# Sheet1.net
KiCad netlist of a schematic drawn in Altium Designer
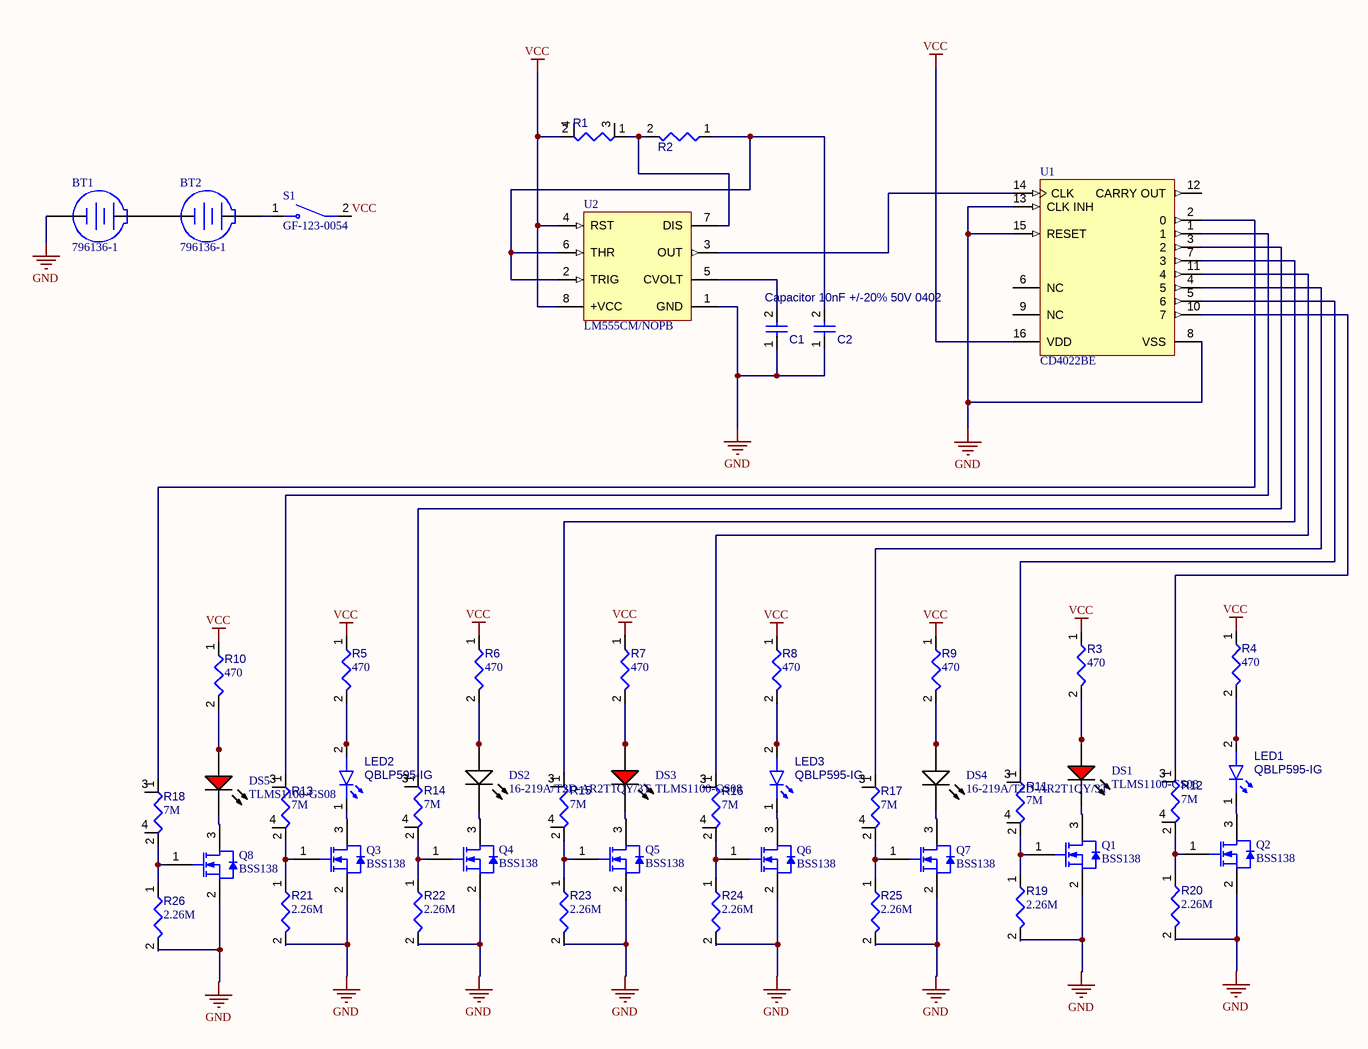
[diagram p0: Sheet1.SchDoc]

(export (version "E")
  (design (tool "Eeschema 10.0.6"))
  (components
    (comp (ref "BT1")
      (value "796136-1")
      (footprint "TECO-796136-1_V")
      (description "Battery Connector, 1 Cell, CR2032, 2-Pin SMD, RoHS, Tape and Reel")
      (fields (field (name "MANUFACTURER") "TE Connectivity"))
      (libsource (lib "Actalent") (part "BATTERY-HOLDER-COIN-2"))
    )
    (comp (ref "BT2")
      (value "796136-1")
      (footprint "TECO-796136-1_V")
      (description "Battery Connector, 1 Cell, CR2032, 2-Pin SMD, RoHS, Tape and Reel")
      (fields (field (name "MANUFACTURER") "TE Connectivity"))
      (libsource (lib "Actalent") (part "BATTERY-HOLDER-COIN-2"))
    )
    (comp (ref "C1")
      (value "Capacitor 10nF +/-20% 50V 0402")
      (footprint "CAPC0402(1005)60_L")
      (description "Chip Capacitor, 10nF +/-20%, 50V, 0402, Thickness 0.6 mm")
      (fields (field (name "TOLERANCE") "5%"))
      (libsource (lib "Actalent") (part "CAP-NP-2"))
    )
    (comp (ref "C2")
      (value "Capacitor 100 nF +/-10% 50 V 0805")
      (footprint "CAPC2013X95X50LL10T25")
      (description "Chip Capacitor, 100 nF, +/- 10%, 50 V, 0805 (2012 Metric)")
      (fields (field (name "TOLERANCE") "10%"))
      (libsource (lib "Actalent") (part "CAP-NP-2"))
    )
    (comp (ref "DS1")
      (value "TLMS1100-GS08")
      (footprint "VISH-TLMX1100_V")
      (description "Red Led, 20mA, 2.1 V, -40 to 100 degC, 2-Pin SMD (0603), RoHS, Tape and Reel")
      (fields (field (name "MANUFACTURER") "Vishay Semiconductor") (field (name "POWER") "90mW"))
      (libsource (lib "Actalent") (part "LED-RED-AK-2"))
    )
    (comp (ref "DS2")
      (value "16-219A/T2D-AR2T1QY/3T")
      (footprint "EVRL-0402-2_V")
      (description "Chip LED, White, 5 V, 10 mA, 30 mW, -40 to 85 degC, 2-Pin SMD (0402), RoHS, Tape and Reel")
      (fields (field (name "POWER") "30mW") (field (name "MANUFACTURER") "Everlight Electronics"))
      (libsource (lib "Actalent") (part "LED-WHITE-AK-2"))
    )
    (comp (ref "DS3")
      (value "TLMS1100-GS08")
      (footprint "VISH-TLMX1100_V")
      (description "Red Led, 20mA, 2.1 V, -40 to 100 degC, 2-Pin SMD (0603), RoHS, Tape and Reel")
      (fields (field (name "MANUFACTURER") "Vishay Semiconductor") (field (name "POWER") "90mW"))
      (libsource (lib "Actalent") (part "LED-RED-AK-2"))
    )
    (comp (ref "DS4")
      (value "16-219A/T2D-AR2T1QY/3T")
      (footprint "EVRL-0402-2_V")
      (description "Chip LED, White, 5 V, 10 mA, 30 mW, -40 to 85 degC, 2-Pin SMD (0402), RoHS, Tape and Reel")
      (fields (field (name "POWER") "30mW") (field (name "MANUFACTURER") "Everlight Electronics"))
      (libsource (lib "Actalent") (part "LED-WHITE-AK-2"))
    )
    (comp (ref "DS5")
      (value "TLMS1100-GS08")
      (footprint "VISH-TLMX1100_V")
      (description "Red Led, 20mA, 2.1 V, -40 to 100 degC, 2-Pin SMD (0603), RoHS, Tape and Reel")
      (fields (field (name "MANUFACTURER") "Vishay Semiconductor") (field (name "POWER") "90mW"))
      (libsource (lib "Actalent") (part "LED-RED-AK-2"))
    )
    (comp (ref "LED1")
      (value "QBLP595-IG")
      (footprint "QTB-QBLP595_V")
      (description "Chip LED 0402, Green, 0.02 A, 3.1 to 3.7 V, -40 to 80 degC, 2-Pin SMD, RoHS, Tape and Reel")
      (libsource (lib "Actalent") (part "LED-KA-2"))
    )
    (comp (ref "LED2")
      (value "QBLP595-IG")
      (footprint "QTB-QBLP595_V")
      (description "Chip LED 0402, Green, 0.02 A, 3.1 to 3.7 V, -40 to 80 degC, 2-Pin SMD, RoHS, Tape and Reel")
      (libsource (lib "Actalent") (part "LED-KA-2"))
    )
    (comp (ref "LED3")
      (value "QBLP595-IG")
      (footprint "QTB-QBLP595_V")
      (description "Chip LED 0402, Green, 0.02 A, 3.1 to 3.7 V, -40 to 80 degC, 2-Pin SMD, RoHS, Tape and Reel")
      (libsource (lib "Actalent") (part "LED-KA-2"))
    )
    (comp (ref "Q1")
      (value "BSS138")
      (footprint "FAIR-SOT23-3_V")
      (fields (field (name "MANUFACTURER") "Fairchild") (field (name "POWER") "360mW"))
      (libsource (lib "Actalent") (part "NEMOS-GSD-3"))
    )
    (comp (ref "Q2")
      (value "BSS138")
      (footprint "FAIR-SOT23-3_V")
      (fields (field (name "MANUFACTURER") "Fairchild") (field (name "POWER") "360mW"))
      (libsource (lib "Actalent") (part "NEMOS-GSD-3"))
    )
    (comp (ref "Q3")
      (value "BSS138")
      (footprint "FAIR-SOT23-3_V")
      (fields (field (name "MANUFACTURER") "Fairchild") (field (name "POWER") "360mW"))
      (libsource (lib "Actalent") (part "NEMOS-GSD-3"))
    )
    (comp (ref "Q4")
      (value "BSS138")
      (footprint "FAIR-SOT23-3_V")
      (fields (field (name "MANUFACTURER") "Fairchild") (field (name "POWER") "360mW"))
      (libsource (lib "Actalent") (part "NEMOS-GSD-3"))
    )
    (comp (ref "Q5")
      (value "BSS138")
      (footprint "FAIR-SOT23-3_V")
      (fields (field (name "MANUFACTURER") "Fairchild") (field (name "POWER") "360mW"))
      (libsource (lib "Actalent") (part "NEMOS-GSD-3"))
    )
    (comp (ref "Q6")
      (value "BSS138")
      (footprint "FAIR-SOT23-3_V")
      (fields (field (name "MANUFACTURER") "Fairchild") (field (name "POWER") "360mW"))
      (libsource (lib "Actalent") (part "NEMOS-GSD-3"))
    )
    (comp (ref "Q7")
      (value "BSS138")
      (footprint "FAIR-SOT23-3_V")
      (fields (field (name "MANUFACTURER") "Fairchild") (field (name "POWER") "360mW"))
      (libsource (lib "Actalent") (part "NEMOS-GSD-3"))
    )
    (comp (ref "Q8")
      (value "BSS138")
      (footprint "FAIR-SOT23-3_V")
      (fields (field (name "MANUFACTURER") "Fairchild") (field (name "POWER") "360mW"))
      (libsource (lib "Actalent") (part "NEMOS-GSD-3"))
    )
    (comp (ref "R1")
      (value "KRL3216T4A-M-R007-F-T1")
      (footprint "SUSUMU-3216T4A")
      (description "RES SMD 0.007 OHM 1W 1206 WIDE")
      (fields (field (name "TOLERANCE") "1%"))
      (libsource (lib "Actalent") (part "KRL3216T4A-M-R007-F-T1"))
    )
    (comp (ref "R2")
      (value "Resistor 1M +/-1 % 0402 63 mW")
      (footprint "RESC0402(1005)_L")
      (description "Chip Resistor, 1 MOhms, +/-1 %, 63 mW, -55 to 155 degC, 0402")
      (fields (field (name "TOLERANCE") "1%") (field (name "POWER") "63mW"))
      (libsource (lib "Actalent") (part "RES-2"))
    )
    (comp (ref "R3")
      (value "470")
      (footprint "RESC0805(2012)_L")
      (description "Chip Resistor, 470 Ohms, +/-5%, 125 mW, -55 to 155 degC, 0805")
      (fields (field (name "TOLERANCE") "5%") (field (name "POWER") "125mW"))
      (libsource (lib "Actalent") (part "RES-2"))
    )
    (comp (ref "R4")
      (value "470")
      (footprint "RESC0805(2012)_L")
      (description "Chip Resistor, 470 Ohms, +/-5%, 125 mW, -55 to 155 degC, 0805")
      (fields (field (name "TOLERANCE") "5%") (field (name "POWER") "125mW"))
      (libsource (lib "Actalent") (part "RES-2"))
    )
    (comp (ref "R5")
      (value "470")
      (footprint "RESC0805(2012)_L")
      (description "Chip Resistor, 470 Ohms, +/-5%, 125 mW, -55 to 155 degC, 0805")
      (fields (field (name "TOLERANCE") "5%") (field (name "POWER") "125mW"))
      (libsource (lib "Actalent") (part "RES-2"))
    )
    (comp (ref "R6")
      (value "470")
      (footprint "RESC0805(2012)_L")
      (description "Chip Resistor, 470 Ohms, +/-5%, 125 mW, -55 to 155 degC, 0805")
      (fields (field (name "TOLERANCE") "5%") (field (name "POWER") "125mW"))
      (libsource (lib "Actalent") (part "RES-2"))
    )
    (comp (ref "R7")
      (value "470")
      (footprint "RESC0805(2012)_L")
      (description "Chip Resistor, 470 Ohms, +/-5%, 125 mW, -55 to 155 degC, 0805")
      (fields (field (name "TOLERANCE") "5%") (field (name "POWER") "125mW"))
      (libsource (lib "Actalent") (part "RES-2"))
    )
    (comp (ref "R8")
      (value "470")
      (footprint "RESC0805(2012)_L")
      (description "Chip Resistor, 470 Ohms, +/-5%, 125 mW, -55 to 155 degC, 0805")
      (fields (field (name "TOLERANCE") "5%") (field (name "POWER") "125mW"))
      (libsource (lib "Actalent") (part "RES-2"))
    )
    (comp (ref "R9")
      (value "470")
      (footprint "RESC0805(2012)_L")
      (description "Chip Resistor, 470 Ohms, +/-5%, 125 mW, -55 to 155 degC, 0805")
      (fields (field (name "TOLERANCE") "5%") (field (name "POWER") "125mW"))
      (libsource (lib "Actalent") (part "RES-2"))
    )
    (comp (ref "R10")
      (value "470")
      (footprint "RESC0805(2012)_L")
      (description "Chip Resistor, 470 Ohms, +/-5%, 125 mW, -55 to 155 degC, 0805")
      (fields (field (name "TOLERANCE") "5%") (field (name "POWER") "125mW"))
      (libsource (lib "Actalent") (part "RES-2"))
    )
    (comp (ref "R11")
      (value "7M")
      (footprint "SUSUMU-3216T4A")
      (description "RES SMD 0.007 OHM 1W 1206 WIDE")
      (fields (field (name "TOLERANCE") "1%") (field (name "Comment") "KRL3216T4A-M-R007-F-T1"))
      (libsource (lib "Actalent") (part "KRL3216T4A-M-R007-F-T1"))
    )
    (comp (ref "R12")
      (value "7M")
      (footprint "SUSUMU-3216T4A")
      (description "RES SMD 0.007 OHM 1W 1206 WIDE")
      (fields (field (name "TOLERANCE") "1%") (field (name "Comment") "KRL3216T4A-M-R007-F-T1"))
      (libsource (lib "Actalent") (part "KRL3216T4A-M-R007-F-T1"))
    )
    (comp (ref "R13")
      (value "7M")
      (footprint "SUSUMU-3216T4A")
      (description "RES SMD 0.007 OHM 1W 1206 WIDE")
      (fields (field (name "TOLERANCE") "1%") (field (name "Comment") "KRL3216T4A-M-R007-F-T1"))
      (libsource (lib "Actalent") (part "KRL3216T4A-M-R007-F-T1"))
    )
    (comp (ref "R14")
      (value "7M")
      (footprint "SUSUMU-3216T4A")
      (description "RES SMD 0.007 OHM 1W 1206 WIDE")
      (fields (field (name "TOLERANCE") "1%") (field (name "Comment") "KRL3216T4A-M-R007-F-T1"))
      (libsource (lib "Actalent") (part "KRL3216T4A-M-R007-F-T1"))
    )
    (comp (ref "R15")
      (value "7M")
      (footprint "SUSUMU-3216T4A")
      (description "RES SMD 0.007 OHM 1W 1206 WIDE")
      (fields (field (name "TOLERANCE") "1%") (field (name "Comment") "KRL3216T4A-M-R007-F-T1"))
      (libsource (lib "Actalent") (part "KRL3216T4A-M-R007-F-T1"))
    )
    (comp (ref "R16")
      (value "7M")
      (footprint "SUSUMU-3216T4A")
      (description "RES SMD 0.007 OHM 1W 1206 WIDE")
      (fields (field (name "TOLERANCE") "1%") (field (name "Comment") "KRL3216T4A-M-R007-F-T1"))
      (libsource (lib "Actalent") (part "KRL3216T4A-M-R007-F-T1"))
    )
    (comp (ref "R17")
      (value "7M")
      (footprint "SUSUMU-3216T4A")
      (description "RES SMD 0.007 OHM 1W 1206 WIDE")
      (fields (field (name "TOLERANCE") "1%") (field (name "Comment") "KRL3216T4A-M-R007-F-T1"))
      (libsource (lib "Actalent") (part "KRL3216T4A-M-R007-F-T1"))
    )
    (comp (ref "R18")
      (value "7M")
      (footprint "SUSUMU-3216T4A")
      (description "RES SMD 0.007 OHM 1W 1206 WIDE")
      (fields (field (name "TOLERANCE") "1%") (field (name "Comment") "KRL3216T4A-M-R007-F-T1"))
      (libsource (lib "Actalent") (part "KRL3216T4A-M-R007-F-T1"))
    )
    (comp (ref "R19")
      (value "2.26M")
      (footprint "RESC0402(1005)_L")
      (description "2M26 0.063W 1% 0402 (1005 Metric)  SMD")
      (fields (field (name "TOLERANCE") "1%") (field (name "POWER") "63mW"))
      (libsource (lib "Actalent") (part "2D26MR2F"))
    )
    (comp (ref "R20")
      (value "2.26M")
      (footprint "RESC0402(1005)_L")
      (description "2M26 0.063W 1% 0402 (1005 Metric)  SMD")
      (fields (field (name "TOLERANCE") "1%") (field (name "POWER") "63mW"))
      (libsource (lib "Actalent") (part "2D26MR2F"))
    )
    (comp (ref "R21")
      (value "2.26M")
      (footprint "RESC0402(1005)_L")
      (description "2M26 0.063W 1% 0402 (1005 Metric)  SMD")
      (fields (field (name "TOLERANCE") "1%") (field (name "POWER") "63mW"))
      (libsource (lib "Actalent") (part "2D26MR2F"))
    )
    (comp (ref "R22")
      (value "2.26M")
      (footprint "RESC0402(1005)_L")
      (description "2M26 0.063W 1% 0402 (1005 Metric)  SMD")
      (fields (field (name "TOLERANCE") "1%") (field (name "POWER") "63mW"))
      (libsource (lib "Actalent") (part "2D26MR2F"))
    )
    (comp (ref "R23")
      (value "2.26M")
      (footprint "RESC0402(1005)_L")
      (description "2M26 0.063W 1% 0402 (1005 Metric)  SMD")
      (fields (field (name "TOLERANCE") "1%") (field (name "POWER") "63mW"))
      (libsource (lib "Actalent") (part "2D26MR2F"))
    )
    (comp (ref "R24")
      (value "2.26M")
      (footprint "RESC0402(1005)_L")
      (description "2M26 0.063W 1% 0402 (1005 Metric)  SMD")
      (fields (field (name "TOLERANCE") "1%") (field (name "POWER") "63mW"))
      (libsource (lib "Actalent") (part "2D26MR2F"))
    )
    (comp (ref "R25")
      (value "2.26M")
      (footprint "RESC0402(1005)_L")
      (description "2M26 0.063W 1% 0402 (1005 Metric)  SMD")
      (fields (field (name "TOLERANCE") "1%") (field (name "POWER") "63mW"))
      (libsource (lib "Actalent") (part "2D26MR2F"))
    )
    (comp (ref "R26")
      (value "2.26M")
      (footprint "RESC0402(1005)_L")
      (description "2M26 0.063W 1% 0402 (1005 Metric)  SMD")
      (fields (field (name "TOLERANCE") "1%") (field (name "POWER") "63mW"))
      (libsource (lib "Actalent") (part "2D26MR2F"))
    )
    (comp (ref "S1")
      (value "GF-123-0054")
      (footprint "SW_GF-123-0054")
      (description "Slide Switch SPST Through Hole")
      (libsource (lib "Actalent") (part "GF-123-0054"))
    )
    (comp (ref "U1")
      (value "CD4022BE")
      (footprint "N0016A")
      (description "CMOS Octal Counter with 8 Decoded Outputs, N0016A, TUBE")
      (fields
        (field (name "MANUFACTURER") "Texas Instruments")
        (field (name "GENERIC PART NUMBER") "CD4022B")
      )
      (libsource (lib "Altium Content Vault") (part "TI-CD4022B-16"))
    )
    (comp (ref "U2")
      (value "LM555CM/NOPB")
      (footprint "D0008A_M")
      (description "Timer, 8-pin Narrow SOIC, Pb-Free")
      (fields (field (name "MANUFACTURER") "Texas Instruments"))
      (libsource (lib "Altium Content Vault") (part "AN-TIMER-LM555-8"))
    )
  )
  (nets
    (net (code "1") (name "GND") (class "Default")
      (node (ref "BT1") (pin "2") (pinfunction "-_2") (pintype "passive"))
      (node (ref "C1") (pin "1") (pinfunction "1_1") (pintype "passive"))
      (node (ref "C2") (pin "1") (pinfunction "1_1") (pintype "passive"))
      (node (ref "Q1") (pin "2") (pinfunction "S_2") (pintype "passive"))
      (node (ref "Q2") (pin "2") (pinfunction "S_2") (pintype "passive"))
      (node (ref "Q3") (pin "2") (pinfunction "S_2") (pintype "passive"))
      (node (ref "Q4") (pin "2") (pinfunction "S_2") (pintype "passive"))
      (node (ref "Q5") (pin "2") (pinfunction "S_2") (pintype "passive"))
      (node (ref "Q6") (pin "2") (pinfunction "S_2") (pintype "passive"))
      (node (ref "Q7") (pin "2") (pinfunction "S_2") (pintype "passive"))
      (node (ref "Q8") (pin "2") (pinfunction "S_2") (pintype "passive"))
      (node (ref "R19") (pin "2") (pinfunction "2_2") (pintype "passive"))
      (node (ref "R20") (pin "2") (pinfunction "2_2") (pintype "passive"))
      (node (ref "R21") (pin "2") (pinfunction "2_2") (pintype "passive"))
      (node (ref "R22") (pin "2") (pinfunction "2_2") (pintype "passive"))
      (node (ref "R23") (pin "2") (pinfunction "2_2") (pintype "passive"))
      (node (ref "R24") (pin "2") (pinfunction "2_2") (pintype "passive"))
      (node (ref "R25") (pin "2") (pinfunction "2_2") (pintype "passive"))
      (node (ref "R26") (pin "2") (pinfunction "2_2") (pintype "passive"))
      (node (ref "U1") (pin "13") (pinfunction "CLK_INH_13") (pintype "input"))
      (node (ref "U1") (pin "15") (pinfunction "RESET_15") (pintype "input"))
      (node (ref "U1") (pin "8") (pinfunction "VSS_8") (pintype "power_in"))
      (node (ref "U2") (pin "1") (pinfunction "GND_1") (pintype "power_in"))
    )
    (net (code "2") (name "Net-(BT1-+)") (class "Default")
      (node (ref "BT1") (pin "1") (pinfunction "+_1") (pintype "passive"))
      (node (ref "BT2") (pin "2") (pinfunction "-_2") (pintype "passive"))
    )
    (net (code "3") (name "Net-(BT2-+)") (class "Default")
      (node (ref "BT2") (pin "1") (pinfunction "+_1") (pintype "passive"))
      (node (ref "S1") (pin "1") (pinfunction "1_1") (pintype "passive"))
    )
    (net (code "4") (name "Net-(DS1-A)") (class "Default")
      (node (ref "DS1") (pin "1") (pinfunction "A_1") (pintype "passive"))
      (node (ref "R3") (pin "2") (pinfunction "2_2") (pintype "passive"))
    )
    (net (code "5") (name "Net-(DS1-K)") (class "Default")
      (node (ref "DS1") (pin "2") (pinfunction "K_2") (pintype "passive"))
      (node (ref "Q1") (pin "3") (pinfunction "D_3") (pintype "passive"))
    )
    (net (code "6") (name "Net-(DS2-A)") (class "Default")
      (node (ref "DS2") (pin "1") (pinfunction "A_1") (pintype "passive"))
      (node (ref "R6") (pin "2") (pinfunction "2_2") (pintype "passive"))
    )
    (net (code "7") (name "Net-(DS2-K)") (class "Default")
      (node (ref "DS2") (pin "2") (pinfunction "K_2") (pintype "passive"))
      (node (ref "Q4") (pin "3") (pinfunction "D_3") (pintype "passive"))
    )
    (net (code "8") (name "Net-(DS3-A)") (class "Default")
      (node (ref "DS3") (pin "1") (pinfunction "A_1") (pintype "passive"))
      (node (ref "R7") (pin "2") (pinfunction "2_2") (pintype "passive"))
    )
    (net (code "9") (name "Net-(DS3-K)") (class "Default")
      (node (ref "DS3") (pin "2") (pinfunction "K_2") (pintype "passive"))
      (node (ref "Q5") (pin "3") (pinfunction "D_3") (pintype "passive"))
    )
    (net (code "10") (name "Net-(DS4-A)") (class "Default")
      (node (ref "DS4") (pin "1") (pinfunction "A_1") (pintype "passive"))
      (node (ref "R9") (pin "2") (pinfunction "2_2") (pintype "passive"))
    )
    (net (code "11") (name "Net-(DS4-K)") (class "Default")
      (node (ref "DS4") (pin "2") (pinfunction "K_2") (pintype "passive"))
      (node (ref "Q7") (pin "3") (pinfunction "D_3") (pintype "passive"))
    )
    (net (code "12") (name "Net-(DS5-A)") (class "Default")
      (node (ref "DS5") (pin "1") (pinfunction "A_1") (pintype "passive"))
      (node (ref "R10") (pin "2") (pinfunction "2_2") (pintype "passive"))
    )
    (net (code "13") (name "Net-(DS5-K)") (class "Default")
      (node (ref "DS5") (pin "2") (pinfunction "K_2") (pintype "passive"))
      (node (ref "Q8") (pin "3") (pinfunction "D_3") (pintype "passive"))
    )
    (net (code "14") (name "Net-(LED1-A)") (class "Default")
      (node (ref "LED1") (pin "2") (pinfunction "A_2") (pintype "passive"))
      (node (ref "R4") (pin "2") (pinfunction "2_2") (pintype "passive"))
    )
    (net (code "15") (name "Net-(LED1-K)") (class "Default")
      (node (ref "LED1") (pin "1") (pinfunction "K_1") (pintype "passive"))
      (node (ref "Q2") (pin "3") (pinfunction "D_3") (pintype "passive"))
    )
    (net (code "16") (name "Net-(LED2-A)") (class "Default")
      (node (ref "LED2") (pin "2") (pinfunction "A_2") (pintype "passive"))
      (node (ref "R5") (pin "2") (pinfunction "2_2") (pintype "passive"))
    )
    (net (code "17") (name "Net-(LED2-K)") (class "Default")
      (node (ref "LED2") (pin "1") (pinfunction "K_1") (pintype "passive"))
      (node (ref "Q3") (pin "3") (pinfunction "D_3") (pintype "passive"))
    )
    (net (code "18") (name "Net-(LED3-A)") (class "Default")
      (node (ref "LED3") (pin "2") (pinfunction "A_2") (pintype "passive"))
      (node (ref "R8") (pin "2") (pinfunction "2_2") (pintype "passive"))
    )
    (net (code "19") (name "Net-(LED3-K)") (class "Default")
      (node (ref "LED3") (pin "1") (pinfunction "K_1") (pintype "passive"))
      (node (ref "Q6") (pin "3") (pinfunction "D_3") (pintype "passive"))
    )
    (net (code "20") (name "Net-(Q1-G)") (class "Default")
      (node (ref "Q1") (pin "1") (pinfunction "G_1") (pintype "passive"))
      (node (ref "R11") (pin "2") (pinfunction "I2_2") (pintype "passive"))
      (node (ref "R19") (pin "1") (pinfunction "1_1") (pintype "passive"))
    )
    (net (code "21") (name "Net-(Q2-G)") (class "Default")
      (node (ref "Q2") (pin "1") (pinfunction "G_1") (pintype "passive"))
      (node (ref "R12") (pin "2") (pinfunction "I2_2") (pintype "passive"))
      (node (ref "R20") (pin "1") (pinfunction "1_1") (pintype "passive"))
    )
    (net (code "22") (name "Net-(Q3-G)") (class "Default")
      (node (ref "Q3") (pin "1") (pinfunction "G_1") (pintype "passive"))
      (node (ref "R13") (pin "2") (pinfunction "I2_2") (pintype "passive"))
      (node (ref "R21") (pin "1") (pinfunction "1_1") (pintype "passive"))
    )
    (net (code "23") (name "Net-(Q4-G)") (class "Default")
      (node (ref "Q4") (pin "1") (pinfunction "G_1") (pintype "passive"))
      (node (ref "R14") (pin "2") (pinfunction "I2_2") (pintype "passive"))
      (node (ref "R22") (pin "1") (pinfunction "1_1") (pintype "passive"))
    )
    (net (code "24") (name "Net-(Q5-G)") (class "Default")
      (node (ref "Q5") (pin "1") (pinfunction "G_1") (pintype "passive"))
      (node (ref "R15") (pin "2") (pinfunction "I2_2") (pintype "passive"))
      (node (ref "R23") (pin "1") (pinfunction "1_1") (pintype "passive"))
    )
    (net (code "25") (name "Net-(Q6-G)") (class "Default")
      (node (ref "Q6") (pin "1") (pinfunction "G_1") (pintype "passive"))
      (node (ref "R16") (pin "2") (pinfunction "I2_2") (pintype "passive"))
      (node (ref "R24") (pin "1") (pinfunction "1_1") (pintype "passive"))
    )
    (net (code "26") (name "Net-(Q7-G)") (class "Default")
      (node (ref "Q7") (pin "1") (pinfunction "G_1") (pintype "passive"))
      (node (ref "R17") (pin "2") (pinfunction "I2_2") (pintype "passive"))
      (node (ref "R25") (pin "1") (pinfunction "1_1") (pintype "passive"))
    )
    (net (code "27") (name "Net-(Q8-G)") (class "Default")
      (node (ref "Q8") (pin "1") (pinfunction "G_1") (pintype "passive"))
      (node (ref "R18") (pin "2") (pinfunction "I2_2") (pintype "passive"))
      (node (ref "R26") (pin "1") (pinfunction "1_1") (pintype "passive"))
    )
    (net (code "28") (name "Net-(R1-I1)") (class "Default")
      (node (ref "R1") (pin "1") (pinfunction "I1_1") (pintype "passive"))
      (node (ref "R2") (pin "2") (pinfunction "2_2") (pintype "passive"))
      (node (ref "U2") (pin "7") (pinfunction "DIS_7") (pintype "open_collector"))
    )
    (net (code "29") (name "Net-(R11-I1)") (class "Default")
      (node (ref "R11") (pin "1") (pinfunction "I1_1") (pintype "passive"))
      (node (ref "U1") (pin "5") (pinfunction "6_5") (pintype "output"))
    )
    (net (code "30") (name "Net-(R12-I1)") (class "Default")
      (node (ref "R12") (pin "1") (pinfunction "I1_1") (pintype "passive"))
      (node (ref "U1") (pin "10") (pinfunction "7_10") (pintype "output"))
    )
    (net (code "31") (name "Net-(R13-I1)") (class "Default")
      (node (ref "R13") (pin "1") (pinfunction "I1_1") (pintype "passive"))
      (node (ref "U1") (pin "1") (pinfunction "1_1") (pintype "output"))
    )
    (net (code "32") (name "Net-(R14-I1)") (class "Default")
      (node (ref "R14") (pin "1") (pinfunction "I1_1") (pintype "passive"))
      (node (ref "U1") (pin "3") (pinfunction "2_3") (pintype "output"))
    )
    (net (code "33") (name "Net-(R15-I1)") (class "Default")
      (node (ref "R15") (pin "1") (pinfunction "I1_1") (pintype "passive"))
      (node (ref "U1") (pin "7") (pinfunction "3_7") (pintype "output"))
    )
    (net (code "34") (name "Net-(R16-I1)") (class "Default")
      (node (ref "R16") (pin "1") (pinfunction "I1_1") (pintype "passive"))
      (node (ref "U1") (pin "11") (pinfunction "4_11") (pintype "output"))
    )
    (net (code "35") (name "Net-(R17-I1)") (class "Default")
      (node (ref "R17") (pin "1") (pinfunction "I1_1") (pintype "passive"))
      (node (ref "U1") (pin "4") (pinfunction "5_4") (pintype "output"))
    )
    (net (code "36") (name "Net-(R18-I1)") (class "Default")
      (node (ref "R18") (pin "1") (pinfunction "I1_1") (pintype "passive"))
      (node (ref "U1") (pin "2") (pinfunction "0_2") (pintype "output"))
    )
    (net (code "37") (name "Net-(U1-CLK)") (class "Default")
      (node (ref "U1") (pin "14") (pinfunction "CLK_14") (pintype "input"))
      (node (ref "U2") (pin "3") (pinfunction "OUT_3") (pintype "output"))
    )
    (net (code "38") (name "Net-(U2-CVOLT)") (class "Default")
      (node (ref "C1") (pin "2") (pinfunction "2_2") (pintype "passive"))
      (node (ref "U2") (pin "5") (pinfunction "CVOLT_5") (pintype "passive"))
    )
    (net (code "39") (name "Net-(U2-THR)") (class "Default")
      (node (ref "C2") (pin "2") (pinfunction "2_2") (pintype "passive"))
      (node (ref "R2") (pin "1") (pinfunction "1_1") (pintype "passive"))
      (node (ref "U2") (pin "2") (pinfunction "TRIG_2") (pintype "input"))
      (node (ref "U2") (pin "6") (pinfunction "THR_6") (pintype "input"))
    )
    (net (code "40") (name "VCC") (class "Default")
      (node (ref "R1") (pin "2") (pinfunction "I2_2") (pintype "passive"))
      (node (ref "R10") (pin "1") (pinfunction "1_1") (pintype "passive"))
      (node (ref "R3") (pin "1") (pinfunction "1_1") (pintype "passive"))
      (node (ref "R4") (pin "1") (pinfunction "1_1") (pintype "passive"))
      (node (ref "R5") (pin "1") (pinfunction "1_1") (pintype "passive"))
      (node (ref "R6") (pin "1") (pinfunction "1_1") (pintype "passive"))
      (node (ref "R7") (pin "1") (pinfunction "1_1") (pintype "passive"))
      (node (ref "R8") (pin "1") (pinfunction "1_1") (pintype "passive"))
      (node (ref "R9") (pin "1") (pinfunction "1_1") (pintype "passive"))
      (node (ref "S1") (pin "2") (pinfunction "2_2") (pintype "passive"))
      (node (ref "U1") (pin "16") (pinfunction "VDD_16") (pintype "power_in"))
      (node (ref "U2") (pin "4") (pinfunction "RST_4") (pintype "input"))
      (node (ref "U2") (pin "8") (pinfunction "+VCC_8") (pintype "power_in"))
    )
    (net (code "41") (name "unconnected-(R1-E1-Pad3)") (class "Default")
      (node (ref "R1") (pin "3") (pinfunction "E1_3") (pintype "passive"))
    )
    (net (code "42") (name "unconnected-(R1-E2-Pad4)") (class "Default")
      (node (ref "R1") (pin "4") (pinfunction "E2_4") (pintype "passive"))
    )
    (net (code "43") (name "unconnected-(R11-E1-Pad3)") (class "Default")
      (node (ref "R11") (pin "3") (pinfunction "E1_3") (pintype "passive"))
    )
    (net (code "44") (name "unconnected-(R11-E2-Pad4)") (class "Default")
      (node (ref "R11") (pin "4") (pinfunction "E2_4") (pintype "passive"))
    )
    (net (code "45") (name "unconnected-(R12-E1-Pad3)") (class "Default")
      (node (ref "R12") (pin "3") (pinfunction "E1_3") (pintype "passive"))
    )
    (net (code "46") (name "unconnected-(R12-E2-Pad4)") (class "Default")
      (node (ref "R12") (pin "4") (pinfunction "E2_4") (pintype "passive"))
    )
    (net (code "47") (name "unconnected-(R13-E1-Pad3)") (class "Default")
      (node (ref "R13") (pin "3") (pinfunction "E1_3") (pintype "passive"))
    )
    (net (code "48") (name "unconnected-(R13-E2-Pad4)") (class "Default")
      (node (ref "R13") (pin "4") (pinfunction "E2_4") (pintype "passive"))
    )
    (net (code "49") (name "unconnected-(R14-E1-Pad3)") (class "Default")
      (node (ref "R14") (pin "3") (pinfunction "E1_3") (pintype "passive"))
    )
    (net (code "50") (name "unconnected-(R14-E2-Pad4)") (class "Default")
      (node (ref "R14") (pin "4") (pinfunction "E2_4") (pintype "passive"))
    )
    (net (code "51") (name "unconnected-(R15-E1-Pad3)") (class "Default")
      (node (ref "R15") (pin "3") (pinfunction "E1_3") (pintype "passive"))
    )
    (net (code "52") (name "unconnected-(R15-E2-Pad4)") (class "Default")
      (node (ref "R15") (pin "4") (pinfunction "E2_4") (pintype "passive"))
    )
    (net (code "53") (name "unconnected-(R16-E1-Pad3)") (class "Default")
      (node (ref "R16") (pin "3") (pinfunction "E1_3") (pintype "passive"))
    )
    (net (code "54") (name "unconnected-(R16-E2-Pad4)") (class "Default")
      (node (ref "R16") (pin "4") (pinfunction "E2_4") (pintype "passive"))
    )
    (net (code "55") (name "unconnected-(R17-E1-Pad3)") (class "Default")
      (node (ref "R17") (pin "3") (pinfunction "E1_3") (pintype "passive"))
    )
    (net (code "56") (name "unconnected-(R17-E2-Pad4)") (class "Default")
      (node (ref "R17") (pin "4") (pinfunction "E2_4") (pintype "passive"))
    )
    (net (code "57") (name "unconnected-(R18-E1-Pad3)") (class "Default")
      (node (ref "R18") (pin "3") (pinfunction "E1_3") (pintype "passive"))
    )
    (net (code "58") (name "unconnected-(R18-E2-Pad4)") (class "Default")
      (node (ref "R18") (pin "4") (pinfunction "E2_4") (pintype "passive"))
    )
    (net (code "59") (name "unconnected-(U1-CARRY_OUT-Pad12)") (class "Default")
      (node (ref "U1") (pin "12") (pinfunction "CARRY_OUT_12") (pintype "output"))
    )
    (net (code "60") (name "unconnected-(U1-NC-Pad6)") (class "Default")
      (node (ref "U1") (pin "6") (pinfunction "NC_6") (pintype "passive"))
    )
    (net (code "61") (name "unconnected-(U1-NC-Pad9)") (class "Default")
      (node (ref "U1") (pin "9") (pinfunction "NC_9") (pintype "passive"))
    )
  )
)
